# Voltage_Regulators.net
KiCad netlist of a schematic drawn in Altium Designer
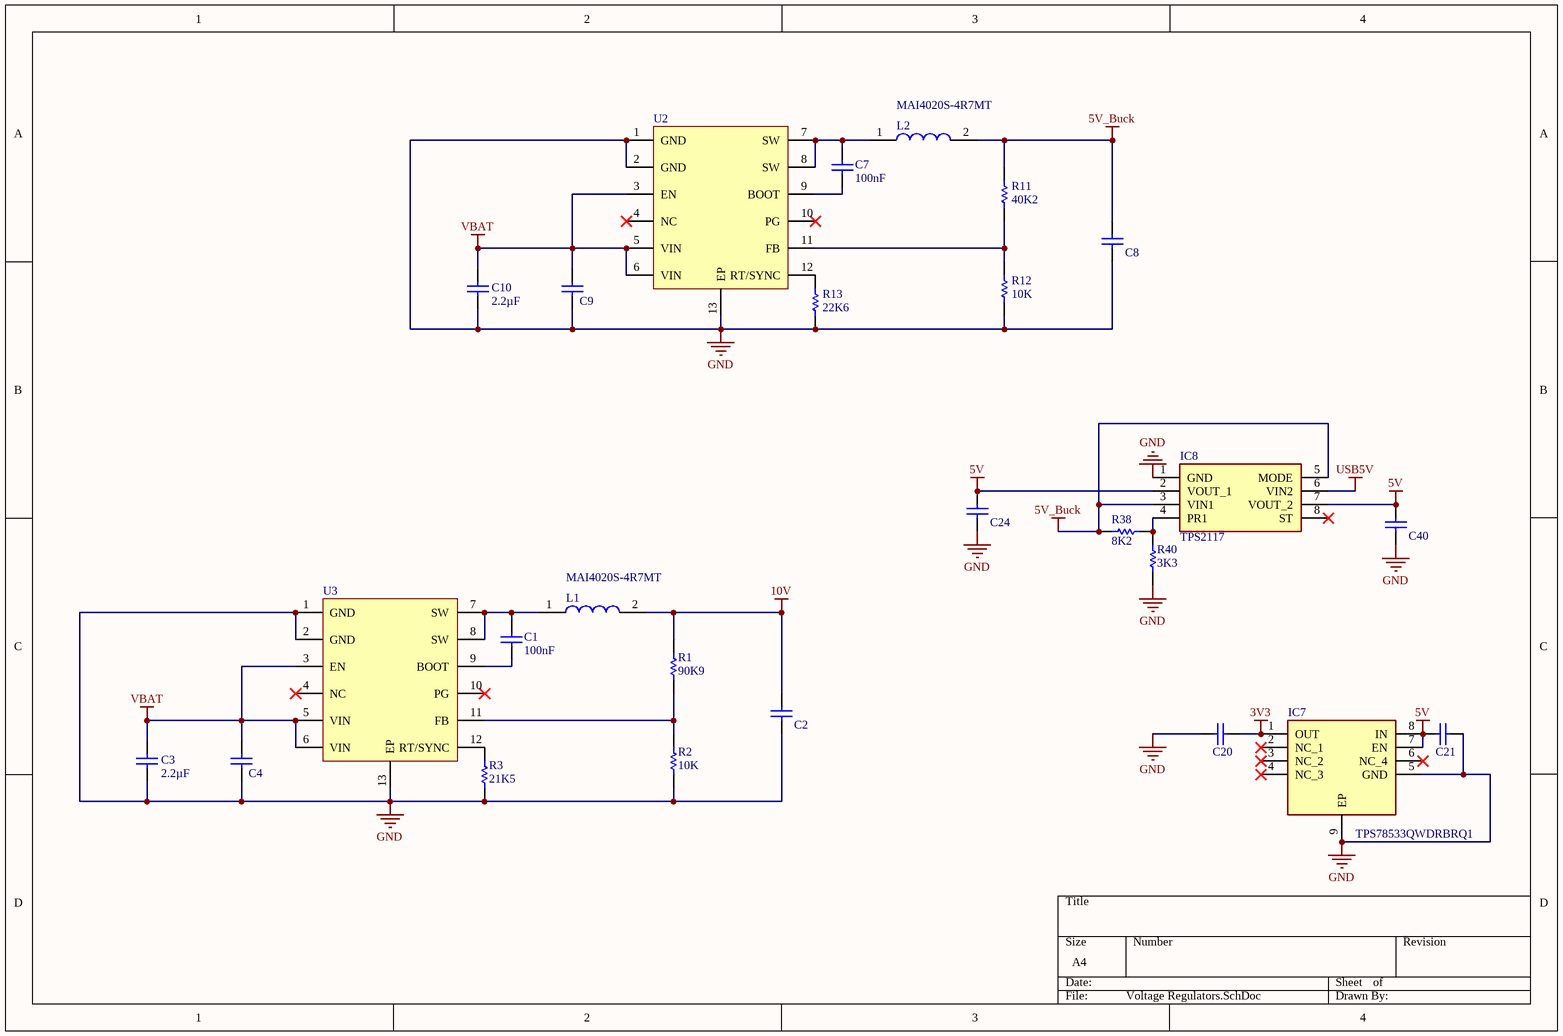
[diagram p0: Voltage Regulators.SchDoc]

(export (version "E")
  (design (tool "Eeschema 10.0.6"))
  (components
    (comp (ref "C1")
      (value "100nF")
      (footprint "0402 cap")
      (libsource (lib "Custom Components") (part "Capacitor 0402 100nF"))
    )
    (comp (ref "C2")
      (value "22µF")
      (footprint "WCAP-CSGP_1210_L3.2W2.5H2.5")
      (description "WCAP-CSGP Multilayer Ceramic Chip Capacitor, General Purpose, size 1210, X7R, 22µF, 25VDC")
      (fields
        (field (name "MANUFACTURER PART NUMBER") "885012209074")
        (field (name "MANUFACTURER") "Wurth Elektronik")
      )
      (libsource (lib "Altium_WCAP-CSGP (rev22f)") (part "885012209074"))
    )
    (comp (ref "C3")
      (value "2.2µF")
      (footprint "WCAP-CSGP_1206_L3.2W1.6H1.6")
      (description "WCAP-CSGP Multilayer Ceramic Chip Capacitor, General Purpose, size 1206, X7R, 2.2µF, 100VDC")
      (fields
        (field (name "MANUFACTURER PART NUMBER") "885012208124")
        (field (name "MANUFACTURER") "Wurth Elektronik")
      )
      (libsource (lib "Altium_WCAP-CSGP (rev22f)") (part "885012208124"))
    )
    (comp (ref "C4")
      (value "100nF")
      (footprint "WCAP-CSGP_0603_L1.6W0.8H0.8_Reflow")
      (description "WCAP-CSGP Multilayer Ceramic Chip Capacitor, General Purpose, size 0603, X7R, 100nF, 50VDC")
      (fields
        (field (name "MANUFACTURER PART NUMBER") "885012206095")
        (field (name "MANUFACTURER") "Wurth Elektronik")
      )
      (libsource (lib "Altium_WCAP-CSGP (rev22f)") (part "885012206095"))
    )
    (comp (ref "C7")
      (value "100nF")
      (footprint "0402 cap")
      (libsource (lib "Custom Components") (part "Capacitor 0402 100nF"))
    )
    (comp (ref "C8")
      (value "47µF")
      (footprint "WCAP-CSGP_1206_L3.2W1.6H1.6")
      (description "WCAP-CSGP Multilayer Ceramic Chip Capacitor, General Purpose, size 1206, X5R, 47µF, 10VDC")
      (fields
        (field (name "MANUFACTURER PART NUMBER") "885012108012")
        (field (name "MANUFACTURER") "Wurth Elektronik")
      )
      (libsource (lib "Altium_WCAP-CSGP (rev22f)") (part "885012108012"))
    )
    (comp (ref "C9")
      (value "100nF")
      (footprint "WCAP-CSGP_0603_L1.6W0.8H0.8_Reflow")
      (description "WCAP-CSGP Multilayer Ceramic Chip Capacitor, General Purpose, size 0603, X7R, 100nF, 50VDC")
      (fields
        (field (name "MANUFACTURER PART NUMBER") "885012206095")
        (field (name "MANUFACTURER") "Wurth Elektronik")
      )
      (libsource (lib "Altium_WCAP-CSGP (rev22f)") (part "885012206095"))
    )
    (comp (ref "C10")
      (value "2.2µF")
      (footprint "WCAP-CSGP_1206_L3.2W1.6H1.6")
      (description "WCAP-CSGP Multilayer Ceramic Chip Capacitor, General Purpose, size 1206, X7R, 2.2µF, 100VDC")
      (fields
        (field (name "MANUFACTURER PART NUMBER") "885012208124")
        (field (name "MANUFACTURER") "Wurth Elektronik")
      )
      (libsource (lib "Altium_WCAP-CSGP (rev22f)") (part "885012208124"))
    )
    (comp (ref "C20")
      (value "1µF")
      (footprint "WCAP-CSGP_0603_L1.6W0.8H0.8_Reflow")
      (description "WCAP-CSGP Multilayer Ceramic Chip Capacitor, General Purpose, size 0603, X7R, 1µF, 10VDC")
      (fields
        (field (name "MANUFACTURER PART NUMBER") "885012206026")
        (field (name "MANUFACTURER") "Wurth Elektronik")
      )
      (libsource (lib "Altium_WCAP-CSGP (rev22f)") (part "885012206026"))
    )
    (comp (ref "C21")
      (value "1µF")
      (footprint "WCAP-CSGP_0603_L1.6W0.8H0.8_Reflow")
      (description "WCAP-CSGP Multilayer Ceramic Chip Capacitor, General Purpose, size 0603, X7R, 1µF, 10VDC")
      (fields
        (field (name "MANUFACTURER PART NUMBER") "885012206026")
        (field (name "MANUFACTURER") "Wurth Elektronik")
      )
      (libsource (lib "Altium_WCAP-CSGP (rev22f)") (part "885012206026"))
    )
    (comp (ref "C24")
      (value "1µF")
      (footprint "WCAP-CSGP_0603_L1.6W0.8H0.8_Reflow")
      (description "WCAP-CSGP Multilayer Ceramic Chip Capacitor, General Purpose, size 0603, X5R, 1µF, 16VDC")
      (fields
        (field (name "MANUFACTURER PART NUMBER") "885012106017")
        (field (name "MANUFACTURER") "Wurth Elektronik")
      )
      (libsource (lib "Altium_WCAP-CSGP (rev22f)") (part "885012106017"))
    )
    (comp (ref "C40")
      (value "1µF")
      (footprint "WCAP-CSGP_0603_L1.6W0.8H0.8_Reflow")
      (description "WCAP-CSGP Multilayer Ceramic Chip Capacitor, General Purpose, size 0603, X5R, 1µF, 16VDC")
      (fields
        (field (name "MANUFACTURER PART NUMBER") "885012106017")
        (field (name "MANUFACTURER") "Wurth Elektronik")
      )
      (libsource (lib "Altium_WCAP-CSGP (rev22f)") (part "885012106017"))
    )
    (comp (ref "IC7")
      (value "TPS78533QWDRBRQ1")
      (footprint "Custom Components:SON65P300X300X100-9N-D")
      (description "Integrated Circuit")
      (fields (field (name "MOUSER PART NUMBER") "595-TPS78533QWDRBRQ1"))
      (libsource (lib "Custom Components") (part "TPS78533QWDRBRQ1"))
    )
    (comp (ref "IC8")
      (value "TPS2117")
      (footprint "Custom Components:SOTFL50P160X60-8N")
      (description "Integrated Circuit")
      (fields
        (field (name "MANUFACTURER_PART_NUMBER") "TPS2116DRLR")
        (field (name "MOUSER PART NUMBER") "595-TPS2116DRLR")
      )
      (libsource (lib "*") (part "TPS2116DRLR"))
    )
    (comp (ref "L1")
      (value "MAI4020S-4R7MT")
      (footprint "MAI4020S-4R7MT")
      (libsource (lib "Custom Components") (part "MAI4020S-4R7MT"))
    )
    (comp (ref "L2")
      (value "MAI4020S-4R7MT")
      (footprint "MAI4020S-4R7MT")
      (libsource (lib "Custom Components") (part "MAI4020S-4R7MT"))
    )
    (comp (ref "R1")
      (value "90K9")
      (footprint "Custom Components:0402 resistor")
      (libsource (lib "Custom Components") (part "Resistor 0402 1K"))
    )
    (comp (ref "R2")
      (value "10K")
      (footprint "Custom Components:0402 resistor")
      (libsource (lib "Custom Components") (part "Resistor 0402 1K"))
    )
    (comp (ref "R3")
      (value "21K5")
      (footprint "Custom Components:0402 resistor")
      (libsource (lib "Custom Components") (part "Resistor 0402 1K"))
    )
    (comp (ref "R11")
      (value "40K2")
      (footprint "RESC0603(1608)_N")
      (description "Chipwiderstand, SMD, Baureihe MC, 1%")
      (fields (field (name "MANUFACTURER") "Multicomp"))
      (libsource (lib "Standardbauteile") (part "Res 33K"))
    )
    (comp (ref "R12")
      (value "10K")
      (footprint "RESC0603(1608)_N")
      (description "Chipwiderstand, SMD, Baureihe MC, 1%")
      (fields (field (name "MANUFACTURER") "Multicomp"))
      (libsource (lib "Standardbauteile") (part "Res 33K"))
    )
    (comp (ref "R13")
      (value "22K6")
      (footprint "RESC0603(1608)_N")
      (description "Chipwiderstand, SMD, Baureihe MC, 1%")
      (fields (field (name "MANUFACTURER") "Multicomp"))
      (libsource (lib "Standardbauteile") (part "Res 33K"))
    )
    (comp (ref "R38")
      (value "8K2")
      (footprint "Custom Components:0402 resistor")
      (libsource (lib "Custom Components") (part "Resistor 0402 1K"))
    )
    (comp (ref "R40")
      (value "3K3")
      (footprint "Custom Components:0402 resistor")
      (libsource (lib "Custom Components") (part "Resistor 0402 1K"))
    )
    (comp (ref "U2")
      (value "2.5A Step Down QFN synchronous")
      (footprint "LMR38025")
      (libsource (lib "Custom Components") (part "LMR38025"))
    )
    (comp (ref "U3")
      (value "2.5A Step Down QFN synchronous")
      (footprint "LMR38025")
      (libsource (lib "Custom Components") (part "LMR38025"))
    )
  )
  (nets
    (net (code "1") (name "3V3") (class "Default")
      (node (ref "C20") (pin "2") (pinfunction "2_2") (pintype "passive"))
      (node (ref "IC7") (pin "1") (pinfunction "OUT_1") (pintype "passive"))
    )
    (net (code "2") (name "5V") (class "Default")
      (node (ref "C21") (pin "1") (pinfunction "1_1") (pintype "passive"))
      (node (ref "C24") (pin "2") (pinfunction "2_2") (pintype "passive"))
      (node (ref "C40") (pin "2") (pinfunction "2_2") (pintype "passive"))
      (node (ref "IC7") (pin "7") (pinfunction "EN_7") (pintype "passive"))
      (node (ref "IC7") (pin "8") (pinfunction "IN_8") (pintype "passive"))
      (node (ref "IC8") (pin "2") (pinfunction "VOUT_1_2") (pintype "passive"))
      (node (ref "IC8") (pin "7") (pinfunction "VOUT_2_7") (pintype "passive"))
    )
    (net (code "3") (name "5V_Buck") (class "Default")
      (node (ref "C8") (pin "2") (pinfunction "2_2") (pintype "passive"))
      (node (ref "IC8") (pin "3") (pinfunction "VIN1_3") (pintype "passive"))
      (node (ref "IC8") (pin "5") (pinfunction "MODE_5") (pintype "passive"))
      (node (ref "L2") (pin "2") (pinfunction "2_2") (pintype "passive"))
      (node (ref "R11") (pin "2") (pinfunction "2_2") (pintype "passive"))
      (node (ref "R38") (pin "1") (pinfunction "1_1") (pintype "passive"))
    )
    (net (code "4") (name "10V") (class "Default")
      (node (ref "C2") (pin "2") (pinfunction "2_2") (pintype "passive"))
      (node (ref "L1") (pin "2") (pinfunction "2_2") (pintype "passive"))
      (node (ref "R1") (pin "2") (pinfunction "2_2") (pintype "passive"))
    )
    (net (code "5") (name "GND") (class "Default")
      (node (ref "C10") (pin "1") (pinfunction "1_1") (pintype "passive"))
      (node (ref "C2") (pin "1") (pinfunction "1_1") (pintype "passive"))
      (node (ref "C20") (pin "1") (pinfunction "1_1") (pintype "passive"))
      (node (ref "C21") (pin "2") (pinfunction "2_2") (pintype "passive"))
      (node (ref "C24") (pin "1") (pinfunction "1_1") (pintype "passive"))
      (node (ref "C3") (pin "1") (pinfunction "1_1") (pintype "passive"))
      (node (ref "C4") (pin "1") (pinfunction "1_1") (pintype "passive"))
      (node (ref "C40") (pin "1") (pinfunction "1_1") (pintype "passive"))
      (node (ref "C8") (pin "1") (pinfunction "1_1") (pintype "passive"))
      (node (ref "C9") (pin "1") (pinfunction "1_1") (pintype "passive"))
      (node (ref "IC7") (pin "5") (pinfunction "GND_5") (pintype "passive"))
      (node (ref "IC7") (pin "9") (pinfunction "EP_9") (pintype "passive"))
      (node (ref "IC8") (pin "1") (pinfunction "GND_1") (pintype "passive"))
      (node (ref "R12") (pin "1") (pinfunction "1_1") (pintype "passive"))
      (node (ref "R13") (pin "1") (pinfunction "1_1") (pintype "passive"))
      (node (ref "R2") (pin "1") (pinfunction "1_1") (pintype "passive"))
      (node (ref "R3") (pin "1") (pinfunction "1_1") (pintype "passive"))
      (node (ref "R40") (pin "1") (pinfunction "1_1") (pintype "passive"))
      (node (ref "U2") (pin "1") (pinfunction "GND_1") (pintype "passive"))
      (node (ref "U2") (pin "13") (pinfunction "EP_13") (pintype "passive"))
      (node (ref "U2") (pin "2") (pinfunction "GND_2") (pintype "passive"))
      (node (ref "U3") (pin "1") (pinfunction "GND_1") (pintype "passive"))
      (node (ref "U3") (pin "13") (pinfunction "EP_13") (pintype "passive"))
      (node (ref "U3") (pin "2") (pinfunction "GND_2") (pintype "passive"))
    )
    (net (code "6") (name "Net-(C1-Pad2)") (class "Default")
      (node (ref "C1") (pin "2") (pinfunction "2_2") (pintype "passive"))
      (node (ref "L1") (pin "1") (pinfunction "1_1") (pintype "passive"))
      (node (ref "U3") (pin "7") (pinfunction "SW_7") (pintype "passive"))
      (node (ref "U3") (pin "8") (pinfunction "SW_8") (pintype "passive"))
    )
    (net (code "7") (name "Net-(C7-Pad2)") (class "Default")
      (node (ref "C7") (pin "2") (pinfunction "2_2") (pintype "passive"))
      (node (ref "L2") (pin "1") (pinfunction "1_1") (pintype "passive"))
      (node (ref "U2") (pin "7") (pinfunction "SW_7") (pintype "passive"))
      (node (ref "U2") (pin "8") (pinfunction "SW_8") (pintype "passive"))
    )
    (net (code "8") (name "Net-(IC8-PR1)") (class "Default")
      (node (ref "IC8") (pin "4") (pinfunction "PR1_4") (pintype "passive"))
      (node (ref "R38") (pin "2") (pinfunction "2_2") (pintype "passive"))
      (node (ref "R40") (pin "2") (pinfunction "2_2") (pintype "passive"))
    )
    (net (code "9") (name "Net-(U2-BOOT)") (class "Default")
      (node (ref "C7") (pin "1") (pinfunction "1_1") (pintype "passive"))
      (node (ref "U2") (pin "9") (pinfunction "BOOT_9") (pintype "passive"))
    )
    (net (code "10") (name "Net-(U2-FB)") (class "Default")
      (node (ref "R11") (pin "1") (pinfunction "1_1") (pintype "passive"))
      (node (ref "R12") (pin "2") (pinfunction "2_2") (pintype "passive"))
      (node (ref "U2") (pin "11") (pinfunction "FB_11") (pintype "passive"))
    )
    (net (code "11") (name "Net-(U2-RT{slash}SYNC)") (class "Default")
      (node (ref "R13") (pin "2") (pinfunction "2_2") (pintype "passive"))
      (node (ref "U2") (pin "12") (pinfunction "RT/SYNC_12") (pintype "passive"))
    )
    (net (code "12") (name "Net-(U3-BOOT)") (class "Default")
      (node (ref "C1") (pin "1") (pinfunction "1_1") (pintype "passive"))
      (node (ref "U3") (pin "9") (pinfunction "BOOT_9") (pintype "passive"))
    )
    (net (code "13") (name "Net-(U3-FB)") (class "Default")
      (node (ref "R1") (pin "1") (pinfunction "1_1") (pintype "passive"))
      (node (ref "R2") (pin "2") (pinfunction "2_2") (pintype "passive"))
      (node (ref "U3") (pin "11") (pinfunction "FB_11") (pintype "passive"))
    )
    (net (code "14") (name "Net-(U3-RT{slash}SYNC)") (class "Default")
      (node (ref "R3") (pin "2") (pinfunction "2_2") (pintype "passive"))
      (node (ref "U3") (pin "12") (pinfunction "RT/SYNC_12") (pintype "passive"))
    )
    (net (code "15") (name "USB5V") (class "Default")
      (node (ref "IC8") (pin "6") (pinfunction "VIN2_6") (pintype "passive"))
    )
    (net (code "16") (name "VBAT") (class "Default")
      (node (ref "C10") (pin "2") (pinfunction "2_2") (pintype "passive"))
      (node (ref "C3") (pin "2") (pinfunction "2_2") (pintype "passive"))
      (node (ref "C4") (pin "2") (pinfunction "2_2") (pintype "passive"))
      (node (ref "C9") (pin "2") (pinfunction "2_2") (pintype "passive"))
      (node (ref "U2") (pin "3") (pinfunction "EN_3") (pintype "passive"))
      (node (ref "U2") (pin "5") (pinfunction "VIN_5") (pintype "passive"))
      (node (ref "U2") (pin "6") (pinfunction "VIN_6") (pintype "passive"))
      (node (ref "U3") (pin "3") (pinfunction "EN_3") (pintype "passive"))
      (node (ref "U3") (pin "5") (pinfunction "VIN_5") (pintype "passive"))
      (node (ref "U3") (pin "6") (pinfunction "VIN_6") (pintype "passive"))
    )
    (net (code "17") (name "unconnected-(IC7-NC_1-Pad2)") (class "Default")
      (node (ref "IC7") (pin "2") (pinfunction "NC_1_2") (pintype "passive+no_connect"))
    )
    (net (code "18") (name "unconnected-(IC7-NC_2-Pad3)") (class "Default")
      (node (ref "IC7") (pin "3") (pinfunction "NC_2_3") (pintype "passive+no_connect"))
    )
    (net (code "19") (name "unconnected-(IC7-NC_3-Pad4)") (class "Default")
      (node (ref "IC7") (pin "4") (pinfunction "NC_3_4") (pintype "passive+no_connect"))
    )
    (net (code "20") (name "unconnected-(IC7-NC_4-Pad6)") (class "Default")
      (node (ref "IC7") (pin "6") (pinfunction "NC_4_6") (pintype "passive+no_connect"))
    )
    (net (code "21") (name "unconnected-(IC8-ST-Pad8)") (class "Default")
      (node (ref "IC8") (pin "8") (pinfunction "ST_8") (pintype "passive+no_connect"))
    )
    (net (code "22") (name "unconnected-(U2-NC-Pad4)") (class "Default")
      (node (ref "U2") (pin "4") (pinfunction "NC_4") (pintype "passive+no_connect"))
    )
    (net (code "23") (name "unconnected-(U2-PG-Pad10)") (class "Default")
      (node (ref "U2") (pin "10") (pinfunction "PG_10") (pintype "passive+no_connect"))
    )
    (net (code "24") (name "unconnected-(U3-NC-Pad4)") (class "Default")
      (node (ref "U3") (pin "4") (pinfunction "NC_4") (pintype "passive+no_connect"))
    )
    (net (code "25") (name "unconnected-(U3-PG-Pad10)") (class "Default")
      (node (ref "U3") (pin "10") (pinfunction "PG_10") (pintype "passive+no_connect"))
    )
  )
)
